# nixie-tube-clock.net
KiCad netlist of a schematic drawn in EAGLE
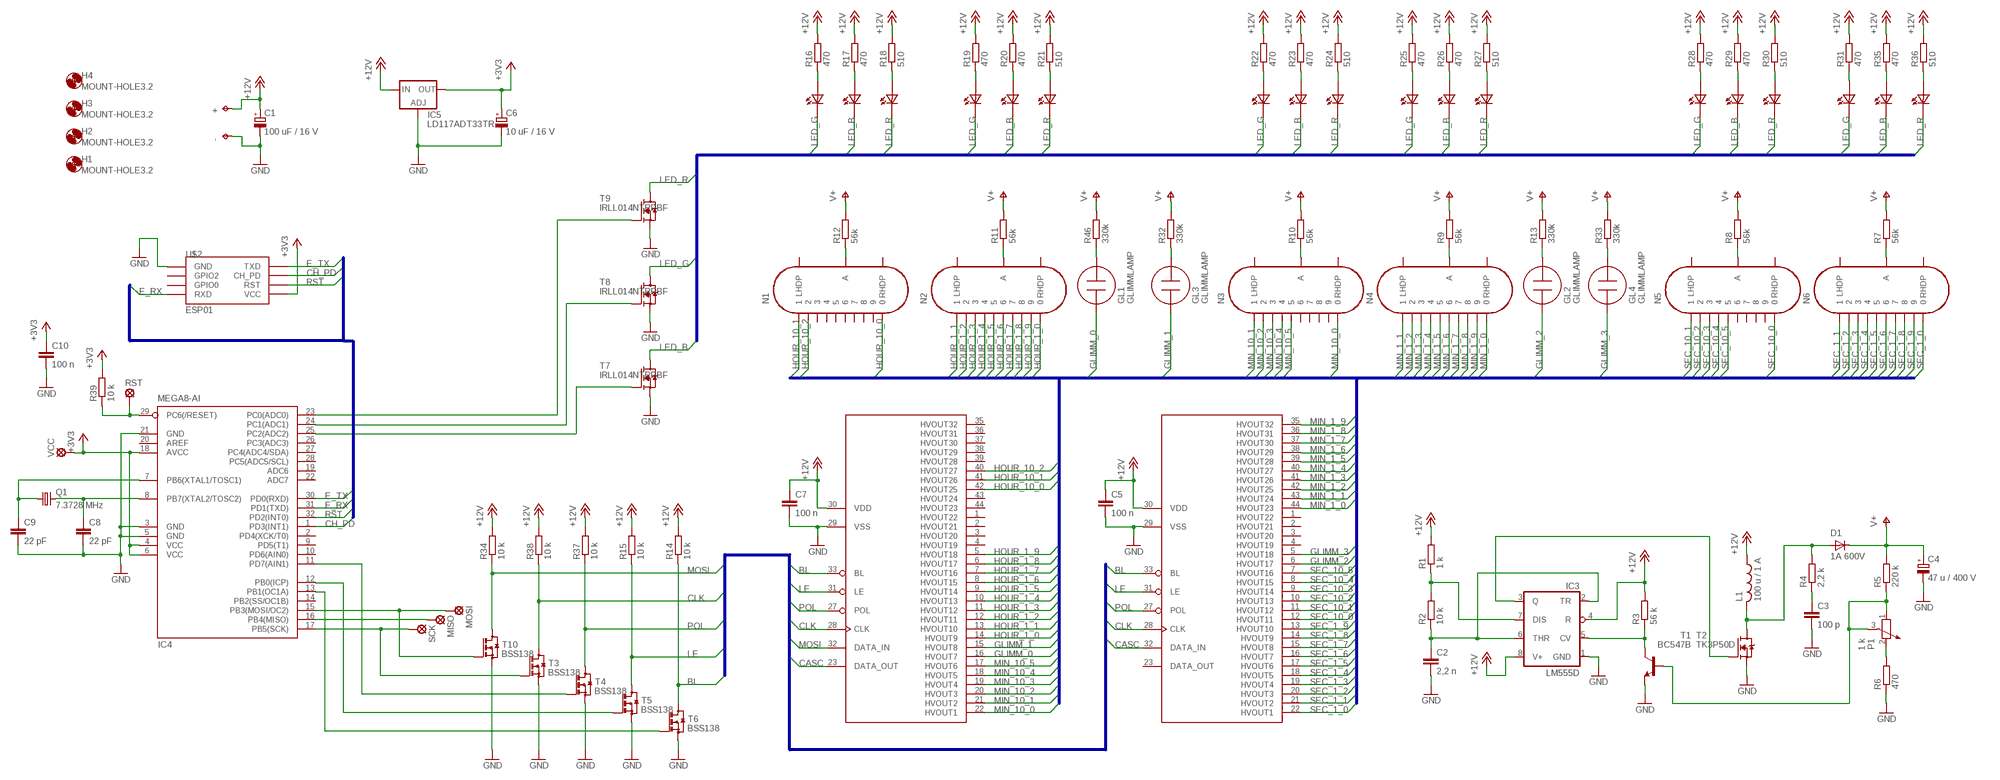
[diagram p0: schematic, sheet 1]

(export (version "E")
  (design (tool "Eeschema 10.0.6"))
  (components
    (comp (ref "+")
      (value "+")
      (footprint "eagle-import:P1-17")
      (libsource (lib "eagle-import") (part "TPPAD1-17"))
    )
    (comp (ref "-")
      (value "-")
      (footprint "eagle-import:P1-17")
      (libsource (lib "eagle-import") (part "TPPAD1-17"))
    )
    (comp (ref "C1")
      (value "100 uF / 16 V")
      (footprint "eagle-import:153CLV-0605")
      (libsource (lib "eagle-import") (part "CPOL-EU153CLV-0605"))
    )
    (comp (ref "C2")
      (value "2,2 n")
      (footprint "eagle-import:C1206")
      (libsource (lib "eagle-import") (part "C-EUC1206"))
    )
    (comp (ref "C3")
      (value "100 p")
      (footprint "eagle-import:C1206")
      (libsource (lib "eagle-import") (part "resistor_C-EUC1206"))
    )
    (comp (ref "C4")
      (value "47 u / 400 V")
      (footprint "eagle-import:E7,5-16")
      (libsource (lib "eagle-import") (part "CPOL-EUE7.5-16"))
    )
    (comp (ref "C5")
      (value "100 n")
      (footprint "eagle-import:C1206")
      (libsource (lib "eagle-import") (part "resistor_C-EUC1206"))
    )
    (comp (ref "C6")
      (value "10 uF / 16 V")
      (footprint "eagle-import:153CLV-0405")
      (libsource (lib "eagle-import") (part "CPOL-EU153CLV-0405"))
    )
    (comp (ref "C7")
      (value "100 n")
      (footprint "eagle-import:C1206")
      (libsource (lib "eagle-import") (part "resistor_C-EUC1206"))
    )
    (comp (ref "C8")
      (value "22 pF")
      (footprint "eagle-import:C1206")
      (libsource (lib "eagle-import") (part "resistor_C-EUC1206"))
    )
    (comp (ref "C9")
      (value "22 pF")
      (footprint "eagle-import:C1206")
      (libsource (lib "eagle-import") (part "resistor_C-EUC1206"))
    )
    (comp (ref "C10")
      (value "100 n")
      (footprint "eagle-import:C1206")
      (libsource (lib "eagle-import") (part "resistor_C-EUC1206"))
    )
    (comp (ref "D1")
      (value "1A 600V")
      (footprint "eagle-import:SMA-DO214AC")
      (libsource (lib "eagle-import") (part "GF1"))
    )
    (comp (ref "GL1")
      (value "GLIMMLAMP")
      (footprint "eagle-import:GLIMMLAMP")
      (libsource (lib "eagle-import") (part "GLIMMLAMP"))
    )
    (comp (ref "GL2")
      (value "GLIMMLAMP")
      (footprint "eagle-import:GLIMMLAMP")
      (libsource (lib "eagle-import") (part "GLIMMLAMP"))
    )
    (comp (ref "GL3")
      (value "GLIMMLAMP")
      (footprint "eagle-import:GLIMMLAMP")
      (libsource (lib "eagle-import") (part "GLIMMLAMP"))
    )
    (comp (ref "GL4")
      (value "GLIMMLAMP")
      (footprint "eagle-import:GLIMMLAMP")
      (libsource (lib "eagle-import") (part "GLIMMLAMP"))
    )
    (comp (ref "H1")
      (value "MOUNT-HOLE3.2")
      (footprint "eagle-import:3,2")
      (libsource (lib "eagle-import") (part "MOUNT-HOLE3.2"))
    )
    (comp (ref "H2")
      (value "MOUNT-HOLE3.2")
      (footprint "eagle-import:3,2")
      (libsource (lib "eagle-import") (part "MOUNT-HOLE3.2"))
    )
    (comp (ref "H3")
      (value "MOUNT-HOLE3.2")
      (footprint "eagle-import:3,2")
      (libsource (lib "eagle-import") (part "MOUNT-HOLE3.2"))
    )
    (comp (ref "H4")
      (value "MOUNT-HOLE3.2")
      (footprint "eagle-import:3,2")
      (libsource (lib "eagle-import") (part "MOUNT-HOLE3.2"))
    )
    (comp (ref "IC1")
      (value "HV5622QC")
      (footprint "eagle-import:PQFP44")
      (libsource (lib "eagle-import") (part "HV5622QC"))
    )
    (comp (ref "IC2")
      (value "HV5622QC")
      (footprint "eagle-import:PQFP44")
      (libsource (lib "eagle-import") (part "HV5622QC"))
    )
    (comp (ref "IC3")
      (value "LM555D")
      (footprint "eagle-import:SO08")
      (libsource (lib "eagle-import") (part "555DLM"))
    )
    (comp (ref "IC4")
      (value "MEGA8-AI")
      (footprint "eagle-import:TQFP32-08")
      (fields (field (name "MPN") "ATMEGA8-16AU"))
      (libsource (lib "eagle-import") (part "MEGA8-AI"))
    )
    (comp (ref "IC5")
      (value "LD117ADT33TR")
      (footprint "eagle-import:DPACK")
      (libsource (lib "eagle-import") (part "LD117A?DT33TR"))
    )
    (comp (ref "L1")
      (value "100 u / 1 A")
      (footprint "eagle-import:L_V_8.7X12_RM5.0")
      (libsource (lib "eagle-import") (part "L_V_8.7X12_RM5.0"))
    )
    (comp (ref "MISO")
      (value "MISO")
      (footprint "eagle-import:SE11")
      (libsource (lib "eagle-import") (part "SE11"))
    )
    (comp (ref "MOSI")
      (value "MOSI")
      (footprint "eagle-import:SE11")
      (libsource (lib "eagle-import") (part "SE11"))
    )
    (comp (ref "N1")
      (value "IN-14")
      (footprint "eagle-import:IN-14")
      (libsource (lib "eagle-import") (part "IN-14"))
    )
    (comp (ref "N2")
      (value "IN-14")
      (footprint "eagle-import:IN-14")
      (libsource (lib "eagle-import") (part "IN-14"))
    )
    (comp (ref "N3")
      (value "IN-14")
      (footprint "eagle-import:IN-14")
      (libsource (lib "eagle-import") (part "IN-14"))
    )
    (comp (ref "N4")
      (value "IN-14")
      (footprint "eagle-import:IN-14")
      (libsource (lib "eagle-import") (part "IN-14"))
    )
    (comp (ref "N5")
      (value "IN-14")
      (footprint "eagle-import:IN-14")
      (libsource (lib "eagle-import") (part "IN-14"))
    )
    (comp (ref "N6")
      (value "IN-14")
      (footprint "eagle-import:IN-14")
      (libsource (lib "eagle-import") (part "IN-14"))
    )
    (comp (ref "P1")
      (value "1 k")
      (footprint "eagle-import:PT-10")
      (libsource (lib "eagle-import") (part "POTENTIOMETER_PT-10"))
    )
    (comp (ref "Q1")
      (value "7.3728 MHz")
      (footprint "eagle-import:HC49_S")
      (libsource (lib "eagle-import") (part "CRYSTALHC49S"))
    )
    (comp (ref "R1")
      (value "1 k")
      (footprint "eagle-import:R1206")
      (libsource (lib "eagle-import") (part "R-EU_R1206"))
    )
    (comp (ref "R2")
      (value "10 k")
      (footprint "eagle-import:R1206")
      (libsource (lib "eagle-import") (part "R-EU_R1206"))
    )
    (comp (ref "R3")
      (value "56 k")
      (footprint "eagle-import:R1206")
      (libsource (lib "eagle-import") (part "R-EU_R1206"))
    )
    (comp (ref "R4")
      (value "2,2 k")
      (footprint "eagle-import:R1206")
      (libsource (lib "eagle-import") (part "R-EU_R1206"))
    )
    (comp (ref "R5")
      (value "220 k")
      (footprint "eagle-import:R1206")
      (libsource (lib "eagle-import") (part "R-EU_R1206"))
    )
    (comp (ref "R6")
      (value "470")
      (footprint "eagle-import:R1206")
      (libsource (lib "eagle-import") (part "R-EU_R1206"))
    )
    (comp (ref "R7")
      (value "56k")
      (footprint "eagle-import:R1206")
      (libsource (lib "eagle-import") (part "R-EU_R1206"))
    )
    (comp (ref "R8")
      (value "56k")
      (footprint "eagle-import:R1206")
      (libsource (lib "eagle-import") (part "R-EU_R1206"))
    )
    (comp (ref "R9")
      (value "56k")
      (footprint "eagle-import:R1206")
      (libsource (lib "eagle-import") (part "R-EU_R1206"))
    )
    (comp (ref "R10")
      (value "56k")
      (footprint "eagle-import:R1206")
      (libsource (lib "eagle-import") (part "R-EU_R1206"))
    )
    (comp (ref "R11")
      (value "56k")
      (footprint "eagle-import:R1206")
      (libsource (lib "eagle-import") (part "R-EU_R1206"))
    )
    (comp (ref "R12")
      (value "56k")
      (footprint "eagle-import:R1206")
      (libsource (lib "eagle-import") (part "R-EU_R1206"))
    )
    (comp (ref "R13")
      (value "330k")
      (footprint "eagle-import:R1206")
      (libsource (lib "eagle-import") (part "R-EU_R1206"))
    )
    (comp (ref "R14")
      (value "10 k")
      (footprint "eagle-import:R1206")
      (libsource (lib "eagle-import") (part "R-EU_R1206"))
    )
    (comp (ref "R15")
      (value "10 k")
      (footprint "eagle-import:R1206")
      (libsource (lib "eagle-import") (part "R-EU_R1206"))
    )
    (comp (ref "R16")
      (value "470")
      (footprint "eagle-import:R1206")
      (libsource (lib "eagle-import") (part "R-EU_R1206"))
    )
    (comp (ref "R17")
      (value "470")
      (footprint "eagle-import:R1206")
      (libsource (lib "eagle-import") (part "R-EU_R1206"))
    )
    (comp (ref "R18")
      (value "510")
      (footprint "eagle-import:R1206")
      (libsource (lib "eagle-import") (part "R-EU_R1206"))
    )
    (comp (ref "R19")
      (value "470")
      (footprint "eagle-import:R1206")
      (libsource (lib "eagle-import") (part "R-EU_R1206"))
    )
    (comp (ref "R20")
      (value "470")
      (footprint "eagle-import:R1206")
      (libsource (lib "eagle-import") (part "R-EU_R1206"))
    )
    (comp (ref "R21")
      (value "510")
      (footprint "eagle-import:R1206")
      (libsource (lib "eagle-import") (part "R-EU_R1206"))
    )
    (comp (ref "R22")
      (value "470")
      (footprint "eagle-import:R1206")
      (libsource (lib "eagle-import") (part "R-EU_R1206"))
    )
    (comp (ref "R23")
      (value "470")
      (footprint "eagle-import:R1206")
      (libsource (lib "eagle-import") (part "R-EU_R1206"))
    )
    (comp (ref "R24")
      (value "510")
      (footprint "eagle-import:R1206")
      (libsource (lib "eagle-import") (part "R-EU_R1206"))
    )
    (comp (ref "R25")
      (value "470")
      (footprint "eagle-import:R1206")
      (libsource (lib "eagle-import") (part "R-EU_R1206"))
    )
    (comp (ref "R26")
      (value "470")
      (footprint "eagle-import:R1206")
      (libsource (lib "eagle-import") (part "R-EU_R1206"))
    )
    (comp (ref "R27")
      (value "510")
      (footprint "eagle-import:R1206")
      (libsource (lib "eagle-import") (part "R-EU_R1206"))
    )
    (comp (ref "R28")
      (value "470")
      (footprint "eagle-import:R1206")
      (libsource (lib "eagle-import") (part "R-EU_R1206"))
    )
    (comp (ref "R29")
      (value "470")
      (footprint "eagle-import:R1206")
      (libsource (lib "eagle-import") (part "R-EU_R1206"))
    )
    (comp (ref "R30")
      (value "510")
      (footprint "eagle-import:R1206")
      (libsource (lib "eagle-import") (part "R-EU_R1206"))
    )
    (comp (ref "R31")
      (value "470")
      (footprint "eagle-import:R1206")
      (libsource (lib "eagle-import") (part "R-EU_R1206"))
    )
    (comp (ref "R32")
      (value "330k")
      (footprint "eagle-import:R1206")
      (libsource (lib "eagle-import") (part "R-EU_R1206"))
    )
    (comp (ref "R33")
      (value "330k")
      (footprint "eagle-import:R1206")
      (libsource (lib "eagle-import") (part "R-EU_R1206"))
    )
    (comp (ref "R34")
      (value "10 k")
      (footprint "eagle-import:R1206")
      (libsource (lib "eagle-import") (part "R-EU_R1206"))
    )
    (comp (ref "R35")
      (value "470")
      (footprint "eagle-import:R1206")
      (libsource (lib "eagle-import") (part "R-EU_R1206"))
    )
    (comp (ref "R36")
      (value "510")
      (footprint "eagle-import:R1206")
      (libsource (lib "eagle-import") (part "R-EU_R1206"))
    )
    (comp (ref "R37")
      (value "10 k")
      (footprint "eagle-import:R1206")
      (libsource (lib "eagle-import") (part "R-EU_R1206"))
    )
    (comp (ref "R38")
      (value "10 k")
      (footprint "eagle-import:R1206")
      (libsource (lib "eagle-import") (part "R-EU_R1206"))
    )
    (comp (ref "R39")
      (value "10 k")
      (footprint "eagle-import:R1206")
      (libsource (lib "eagle-import") (part "R-EU_R1206"))
    )
    (comp (ref "R46")
      (value "330k")
      (footprint "eagle-import:R1206")
      (libsource (lib "eagle-import") (part "R-EU_R1206"))
    )
    (comp (ref "RST")
      (value "RST")
      (footprint "eagle-import:SE11")
      (libsource (lib "eagle-import") (part "SE11"))
    )
    (comp (ref "SCK")
      (value "SCK")
      (footprint "eagle-import:SE11")
      (libsource (lib "eagle-import") (part "SE11"))
    )
    (comp (ref "T1")
      (value "BC547B")
      (footprint "eagle-import:SOT23-BEC")
      (libsource (lib "eagle-import") (part "-NPN-SOT23-BECBC817"))
    )
    (comp (ref "T2")
      (value "TK3P50D")
      (footprint "eagle-import:TO252")
      (libsource (lib "eagle-import") (part "IRFR320PBF"))
    )
    (comp (ref "T3")
      (value "BSS138")
      (footprint "eagle-import:SOT23")
      (libsource (lib "eagle-import") (part "BSS123"))
    )
    (comp (ref "T4")
      (value "BSS138")
      (footprint "eagle-import:SOT23")
      (libsource (lib "eagle-import") (part "BSS123"))
    )
    (comp (ref "T5")
      (value "BSS138")
      (footprint "eagle-import:SOT23")
      (libsource (lib "eagle-import") (part "BSS123"))
    )
    (comp (ref "T6")
      (value "BSS138")
      (footprint "eagle-import:SOT23")
      (libsource (lib "eagle-import") (part "BSS123"))
    )
    (comp (ref "T7")
      (value "IRLL014NTRPBF")
      (footprint "eagle-import:SOT223")
      (libsource (lib "eagle-import") (part "IRLL014NTRPBF"))
    )
    (comp (ref "T8")
      (value "IRLL014NTRPBF")
      (footprint "eagle-import:SOT223")
      (libsource (lib "eagle-import") (part "IRLL014NTRPBF"))
    )
    (comp (ref "T9")
      (value "IRLL014NTRPBF")
      (footprint "eagle-import:SOT223")
      (libsource (lib "eagle-import") (part "IRLL014NTRPBF"))
    )
    (comp (ref "T10")
      (value "BSS138")
      (footprint "eagle-import:SOT23")
      (libsource (lib "eagle-import") (part "BSS123"))
    )
    (comp (ref "U$1")
      (value "OF-SMD5060RGB")
      (footprint "eagle-import:OF-SMD5060RGB")
      (libsource (lib "eagle-import") (part "OF-SMD5060RGB"))
    )
    (comp (ref "U$2")
      (value "ESP01")
      (footprint "eagle-import:ESP01")
      (libsource (lib "eagle-import") (part "ESP01"))
    )
    (comp (ref "U$3")
      (value "OF-SMD5060RGB")
      (footprint "eagle-import:OF-SMD5060RGB")
      (libsource (lib "eagle-import") (part "OF-SMD5060RGB"))
    )
    (comp (ref "U$4")
      (value "OF-SMD5060RGB")
      (footprint "eagle-import:OF-SMD5060RGB")
      (libsource (lib "eagle-import") (part "OF-SMD5060RGB"))
    )
    (comp (ref "U$5")
      (value "OF-SMD5060RGB")
      (footprint "eagle-import:OF-SMD5060RGB")
      (libsource (lib "eagle-import") (part "OF-SMD5060RGB"))
    )
    (comp (ref "U$6")
      (value "OF-SMD5060RGB")
      (footprint "eagle-import:OF-SMD5060RGB")
      (libsource (lib "eagle-import") (part "OF-SMD5060RGB"))
    )
    (comp (ref "U$7")
      (value "OF-SMD5060RGB")
      (footprint "eagle-import:OF-SMD5060RGB")
      (libsource (lib "eagle-import") (part "OF-SMD5060RGB"))
    )
    (comp (ref "VCC")
      (value "VCC")
      (footprint "eagle-import:SE11")
      (libsource (lib "eagle-import") (part "SE11"))
    )
  )
  (nets
    (net (code "1") (name "+3V3") (class "Default")
      (node (ref "C10") (pin "1") (pinfunction "1_1") (pintype "passive"))
      (node (ref "C6") (pin "+") (pinfunction "+_+") (pintype "passive"))
      (node (ref "IC4") (pin "18") (pinfunction "AVCC_18") (pintype "power_in"))
      (node (ref "IC4") (pin "4") (pinfunction "VCC_4") (pintype "power_in"))
      (node (ref "IC4") (pin "6") (pinfunction "VCC_6") (pintype "power_in"))
      (node (ref "IC5") (pin "4") (pinfunction "OUT_4") (pintype "passive"))
      (node (ref "R39") (pin "2") (pinfunction "2_2") (pintype "passive"))
      (node (ref "U$2") (pin "VCC") (pinfunction "VCC_VCC") (pintype "bidirectional"))
      (node (ref "VCC") (pin "MP") (pinfunction "MP_MP") (pintype "passive"))
    )
    (net (code "2") (name "+12V") (class "Default")
      (node (ref "+") (pin "TP") (pinfunction "TP_TP") (pintype "input"))
      (node (ref "C1") (pin "+") (pinfunction "+_+") (pintype "passive"))
      (node (ref "C5") (pin "1") (pinfunction "1_1") (pintype "passive"))
      (node (ref "C7") (pin "1") (pinfunction "1_1") (pintype "passive"))
      (node (ref "IC1") (pin "30") (pinfunction "VDD_30") (pintype "power_in"))
      (node (ref "IC2") (pin "30") (pinfunction "VDD_30") (pintype "power_in"))
      (node (ref "IC3") (pin "4") (pinfunction "R_4") (pintype "input"))
      (node (ref "IC3") (pin "8") (pinfunction "V+_8") (pintype "power_in"))
      (node (ref "IC5") (pin "3") (pinfunction "IN_3") (pintype "input"))
      (node (ref "L1") (pin "P$1") (pinfunction "1_P$1") (pintype "passive"))
      (node (ref "R1") (pin "2") (pinfunction "2_2") (pintype "passive"))
      (node (ref "R14") (pin "2") (pinfunction "2_2") (pintype "passive"))
      (node (ref "R15") (pin "2") (pinfunction "2_2") (pintype "passive"))
      (node (ref "R16") (pin "2") (pinfunction "2_2") (pintype "passive"))
      (node (ref "R17") (pin "2") (pinfunction "2_2") (pintype "passive"))
      (node (ref "R18") (pin "2") (pinfunction "2_2") (pintype "passive"))
      (node (ref "R19") (pin "2") (pinfunction "2_2") (pintype "passive"))
      (node (ref "R20") (pin "2") (pinfunction "2_2") (pintype "passive"))
      (node (ref "R21") (pin "2") (pinfunction "2_2") (pintype "passive"))
      (node (ref "R22") (pin "2") (pinfunction "2_2") (pintype "passive"))
      (node (ref "R23") (pin "2") (pinfunction "2_2") (pintype "passive"))
      (node (ref "R24") (pin "2") (pinfunction "2_2") (pintype "passive"))
      (node (ref "R25") (pin "2") (pinfunction "2_2") (pintype "passive"))
      (node (ref "R26") (pin "2") (pinfunction "2_2") (pintype "passive"))
      (node (ref "R27") (pin "2") (pinfunction "2_2") (pintype "passive"))
      (node (ref "R28") (pin "2") (pinfunction "2_2") (pintype "passive"))
      (node (ref "R29") (pin "2") (pinfunction "2_2") (pintype "passive"))
      (node (ref "R3") (pin "2") (pinfunction "2_2") (pintype "passive"))
      (node (ref "R30") (pin "2") (pinfunction "2_2") (pintype "passive"))
      (node (ref "R31") (pin "2") (pinfunction "2_2") (pintype "passive"))
      (node (ref "R34") (pin "2") (pinfunction "2_2") (pintype "passive"))
      (node (ref "R35") (pin "2") (pinfunction "2_2") (pintype "passive"))
      (node (ref "R36") (pin "2") (pinfunction "2_2") (pintype "passive"))
      (node (ref "R37") (pin "2") (pinfunction "2_2") (pintype "passive"))
      (node (ref "R38") (pin "2") (pinfunction "2_2") (pintype "passive"))
    )
    (net (code "3") (name "/BL") (class "Default")
      (node (ref "IC1") (pin "33") (pinfunction "BL_33") (pintype "input"))
      (node (ref "IC2") (pin "33") (pinfunction "BL_33") (pintype "input"))
      (node (ref "R14") (pin "1") (pinfunction "1_1") (pintype "passive"))
      (node (ref "T6") (pin "3") (pinfunction "D_3") (pintype "passive"))
    )
    (net (code "4") (name "/CASC") (class "Default")
      (node (ref "IC1") (pin "23") (pinfunction "DATA_OUT_23") (pintype "output"))
      (node (ref "IC2") (pin "32") (pinfunction "DATA_IN_32") (pintype "input"))
    )
    (net (code "5") (name "/CH_PD") (class "Default")
      (node (ref "IC4") (pin "1") (pinfunction "PD3(INT1)_1") (pintype "bidirectional"))
      (node (ref "U$2") (pin "CH_PD") (pinfunction "CH_PD_CH_PD") (pintype "bidirectional"))
    )
    (net (code "6") (name "/CLK") (class "Default")
      (node (ref "IC1") (pin "28") (pinfunction "CLK_28") (pintype "input"))
      (node (ref "IC2") (pin "28") (pinfunction "CLK_28") (pintype "input"))
      (node (ref "R38") (pin "1") (pinfunction "1_1") (pintype "passive"))
      (node (ref "T3") (pin "3") (pinfunction "D_3") (pintype "passive"))
    )
    (net (code "7") (name "/E_RX") (class "Default")
      (node (ref "IC4") (pin "31") (pinfunction "PD1(TXD)_31") (pintype "bidirectional"))
      (node (ref "U$2") (pin "RX") (pinfunction "RXD_RX") (pintype "bidirectional"))
    )
    (net (code "8") (name "/E_TX") (class "Default")
      (node (ref "IC4") (pin "30") (pinfunction "PD0(RXD)_30") (pintype "bidirectional"))
      (node (ref "U$2") (pin "TX") (pinfunction "TXD_TX") (pintype "bidirectional"))
    )
    (net (code "9") (name "/GLIMM_0") (class "Default")
      (node (ref "GL1") (pin "C") (pinfunction "P$2_C") (pintype "passive"))
      (node (ref "IC1") (pin "16") (pinfunction "HVOUT7_16") (pintype "bidirectional"))
    )
    (net (code "10") (name "/GLIMM_1") (class "Default")
      (node (ref "GL3") (pin "C") (pinfunction "P$2_C") (pintype "passive"))
      (node (ref "IC1") (pin "15") (pinfunction "HVOUT8_15") (pintype "bidirectional"))
    )
    (net (code "11") (name "/GLIMM_2") (class "Default")
      (node (ref "GL2") (pin "C") (pinfunction "P$2_C") (pintype "passive"))
      (node (ref "IC2") (pin "6") (pinfunction "HVOUT17_6") (pintype "bidirectional"))
    )
    (net (code "12") (name "/GLIMM_3") (class "Default")
      (node (ref "GL4") (pin "C") (pinfunction "P$2_C") (pintype "passive"))
      (node (ref "IC2") (pin "5") (pinfunction "HVOUT18_5") (pintype "bidirectional"))
    )
    (net (code "13") (name "/HOUR_1_0") (class "Default")
      (node (ref "IC1") (pin "14") (pinfunction "HVOUT9_14") (pintype "bidirectional"))
      (node (ref "N2") (pin "0") (pinfunction "0_0") (pintype "bidirectional"))
    )
    (net (code "14") (name "/HOUR_1_1") (class "Default")
      (node (ref "IC1") (pin "13") (pinfunction "HVOUT10_13") (pintype "bidirectional"))
      (node (ref "N2") (pin "1") (pinfunction "1_1") (pintype "bidirectional"))
    )
    (net (code "15") (name "/HOUR_1_2") (class "Default")
      (node (ref "IC1") (pin "12") (pinfunction "HVOUT11_12") (pintype "bidirectional"))
      (node (ref "N2") (pin "2") (pinfunction "2_2") (pintype "bidirectional"))
    )
    (net (code "16") (name "/HOUR_1_3") (class "Default")
      (node (ref "IC1") (pin "11") (pinfunction "HVOUT12_11") (pintype "bidirectional"))
      (node (ref "N2") (pin "3") (pinfunction "3_3") (pintype "bidirectional"))
    )
    (net (code "17") (name "/HOUR_1_4") (class "Default")
      (node (ref "IC1") (pin "10") (pinfunction "HVOUT13_10") (pintype "bidirectional"))
      (node (ref "N2") (pin "4") (pinfunction "4_4") (pintype "bidirectional"))
    )
    (net (code "18") (name "/HOUR_1_5") (class "Default")
      (node (ref "IC1") (pin "9") (pinfunction "HVOUT14_9") (pintype "bidirectional"))
      (node (ref "N2") (pin "5") (pinfunction "5_5") (pintype "bidirectional"))
    )
    (net (code "19") (name "/HOUR_1_6") (class "Default")
      (node (ref "IC1") (pin "8") (pinfunction "HVOUT15_8") (pintype "bidirectional"))
      (node (ref "N2") (pin "6") (pinfunction "6_6") (pintype "bidirectional"))
    )
    (net (code "20") (name "/HOUR_1_7") (class "Default")
      (node (ref "IC1") (pin "7") (pinfunction "HVOUT16_7") (pintype "bidirectional"))
      (node (ref "N2") (pin "7") (pinfunction "7_7") (pintype "bidirectional"))
    )
    (net (code "21") (name "/HOUR_1_8") (class "Default")
      (node (ref "IC1") (pin "6") (pinfunction "HVOUT17_6") (pintype "bidirectional"))
      (node (ref "N2") (pin "8") (pinfunction "8_8") (pintype "bidirectional"))
    )
    (net (code "22") (name "/HOUR_1_9") (class "Default")
      (node (ref "IC1") (pin "5") (pinfunction "HVOUT18_5") (pintype "bidirectional"))
      (node (ref "N2") (pin "9") (pinfunction "9_9") (pintype "bidirectional"))
    )
    (net (code "23") (name "/HOUR_10_0") (class "Default")
      (node (ref "IC1") (pin "42") (pinfunction "HVOUT25_42") (pintype "bidirectional"))
      (node (ref "N1") (pin "0") (pinfunction "0_0") (pintype "bidirectional"))
    )
    (net (code "24") (name "/HOUR_10_1") (class "Default")
      (node (ref "IC1") (pin "41") (pinfunction "HVOUT26_41") (pintype "bidirectional"))
      (node (ref "N1") (pin "1") (pinfunction "1_1") (pintype "bidirectional"))
    )
    (net (code "25") (name "/HOUR_10_2") (class "Default")
      (node (ref "IC1") (pin "40") (pinfunction "HVOUT27_40") (pintype "bidirectional"))
      (node (ref "N1") (pin "2") (pinfunction "2_2") (pintype "bidirectional"))
    )
    (net (code "26") (name "/LE") (class "Default")
      (node (ref "IC1") (pin "31") (pinfunction "LE_31") (pintype "input"))
      (node (ref "IC2") (pin "31") (pinfunction "LE_31") (pintype "input"))
      (node (ref "R15") (pin "1") (pinfunction "1_1") (pintype "passive"))
      (node (ref "T5") (pin "3") (pinfunction "D_3") (pintype "passive"))
    )
    (net (code "27") (name "/LED_B") (class "Default")
      (node (ref "T7") (pin "2") (pinfunction "D_2") (pintype "passive"))
      (node (ref "T7") (pin "4") (pinfunction "D_4") (pintype "passive"))
      (node (ref "U$1") (pin "B_CATH") (pinfunction "CATH_B_CATH") (pintype "bidirectional"))
      (node (ref "U$3") (pin "B_CATH") (pinfunction "CATH_B_CATH") (pintype "bidirectional"))
      (node (ref "U$4") (pin "B_CATH") (pinfunction "CATH_B_CATH") (pintype "bidirectional"))
      (node (ref "U$5") (pin "B_CATH") (pinfunction "CATH_B_CATH") (pintype "bidirectional"))
      (node (ref "U$6") (pin "B_CATH") (pinfunction "CATH_B_CATH") (pintype "bidirectional"))
      (node (ref "U$7") (pin "B_CATH") (pinfunction "CATH_B_CATH") (pintype "bidirectional"))
    )
    (net (code "28") (name "/LED_G") (class "Default")
      (node (ref "T8") (pin "2") (pinfunction "D_2") (pintype "passive"))
      (node (ref "T8") (pin "4") (pinfunction "D_4") (pintype "passive"))
      (node (ref "U$1") (pin "G_CATH") (pinfunction "CATH_G_CATH") (pintype "bidirectional"))
      (node (ref "U$3") (pin "G_CATH") (pinfunction "CATH_G_CATH") (pintype "bidirectional"))
      (node (ref "U$4") (pin "G_CATH") (pinfunction "CATH_G_CATH") (pintype "bidirectional"))
      (node (ref "U$5") (pin "G_CATH") (pinfunction "CATH_G_CATH") (pintype "bidirectional"))
      (node (ref "U$6") (pin "G_CATH") (pinfunction "CATH_G_CATH") (pintype "bidirectional"))
      (node (ref "U$7") (pin "G_CATH") (pinfunction "CATH_G_CATH") (pintype "bidirectional"))
    )
    (net (code "29") (name "/LED_R") (class "Default")
      (node (ref "T9") (pin "2") (pinfunction "D_2") (pintype "passive"))
      (node (ref "T9") (pin "4") (pinfunction "D_4") (pintype "passive"))
      (node (ref "U$1") (pin "R_CATH") (pinfunction "CATH_R_CATH") (pintype "bidirectional"))
      (node (ref "U$3") (pin "R_CATH") (pinfunction "CATH_R_CATH") (pintype "bidirectional"))
      (node (ref "U$4") (pin "R_CATH") (pinfunction "CATH_R_CATH") (pintype "bidirectional"))
      (node (ref "U$5") (pin "R_CATH") (pinfunction "CATH_R_CATH") (pintype "bidirectional"))
      (node (ref "U$6") (pin "R_CATH") (pinfunction "CATH_R_CATH") (pintype "bidirectional"))
      (node (ref "U$7") (pin "R_CATH") (pinfunction "CATH_R_CATH") (pintype "bidirectional"))
    )
    (net (code "30") (name "/MIN_1_0") (class "Default")
      (node (ref "IC2") (pin "44") (pinfunction "HVOUT23_44") (pintype "bidirectional"))
      (node (ref "N4") (pin "0") (pinfunction "0_0") (pintype "bidirectional"))
    )
    (net (code "31") (name "/MIN_1_1") (class "Default")
      (node (ref "IC2") (pin "43") (pinfunction "HVOUT24_43") (pintype "bidirectional"))
      (node (ref "N4") (pin "1") (pinfunction "1_1") (pintype "bidirectional"))
    )
    (net (code "32") (name "/MIN_1_2") (class "Default")
      (node (ref "IC2") (pin "42") (pinfunction "HVOUT25_42") (pintype "bidirectional"))
      (node (ref "N4") (pin "2") (pinfunction "2_2") (pintype "bidirectional"))
    )
    (net (code "33") (name "/MIN_1_3") (class "Default")
      (node (ref "IC2") (pin "41") (pinfunction "HVOUT26_41") (pintype "bidirectional"))
      (node (ref "N4") (pin "3") (pinfunction "3_3") (pintype "bidirectional"))
    )
    (net (code "34") (name "/MIN_1_4") (class "Default")
      (node (ref "IC2") (pin "40") (pinfunction "HVOUT27_40") (pintype "bidirectional"))
      (node (ref "N4") (pin "4") (pinfunction "4_4") (pintype "bidirectional"))
    )
    (net (code "35") (name "/MIN_1_5") (class "Default")
      (node (ref "IC2") (pin "39") (pinfunction "HVOUT28_39") (pintype "bidirectional"))
      (node (ref "N4") (pin "5") (pinfunction "5_5") (pintype "bidirectional"))
    )
    (net (code "36") (name "/MIN_1_6") (class "Default")
      (node (ref "IC2") (pin "38") (pinfunction "HVOUT29_38") (pintype "bidirectional"))
      (node (ref "N4") (pin "6") (pinfunction "6_6") (pintype "bidirectional"))
    )
    (net (code "37") (name "/MIN_1_7") (class "Default")
      (node (ref "IC2") (pin "37") (pinfunction "HVOUT30_37") (pintype "bidirectional"))
      (node (ref "N4") (pin "7") (pinfunction "7_7") (pintype "bidirectional"))
    )
    (net (code "38") (name "/MIN_1_8") (class "Default")
      (node (ref "IC2") (pin "36") (pinfunction "HVOUT31_36") (pintype "bidirectional"))
      (node (ref "N4") (pin "8") (pinfunction "8_8") (pintype "bidirectional"))
    )
    (net (code "39") (name "/MIN_1_9") (class "Default")
      (node (ref "IC2") (pin "35") (pinfunction "HVOUT32_35") (pintype "bidirectional"))
      (node (ref "N4") (pin "9") (pinfunction "9_9") (pintype "bidirectional"))
    )
    (net (code "40") (name "/MIN_10_0") (class "Default")
      (node (ref "IC1") (pin "22") (pinfunction "HVOUT1_22") (pintype "bidirectional"))
      (node (ref "N3") (pin "0") (pinfunction "0_0") (pintype "bidirectional"))
    )
    (net (code "41") (name "/MIN_10_1") (class "Default")
      (node (ref "IC1") (pin "21") (pinfunction "HVOUT2_21") (pintype "bidirectional"))
      (node (ref "N3") (pin "1") (pinfunction "1_1") (pintype "bidirectional"))
    )
    (net (code "42") (name "/MIN_10_2") (class "Default")
      (node (ref "IC1") (pin "20") (pinfunction "HVOUT3_20") (pintype "bidirectional"))
      (node (ref "N3") (pin "2") (pinfunction "2_2") (pintype "bidirectional"))
    )
    (net (code "43") (name "/MIN_10_3") (class "Default")
      (node (ref "IC1") (pin "19") (pinfunction "HVOUT4_19") (pintype "bidirectional"))
      (node (ref "N3") (pin "3") (pinfunction "3_3") (pintype "bidirectional"))
    )
    (net (code "44") (name "/MIN_10_4") (class "Default")
      (node (ref "IC1") (pin "18") (pinfunction "HVOUT5_18") (pintype "bidirectional"))
      (node (ref "N3") (pin "4") (pinfunction "4_4") (pintype "bidirectional"))
    )
    (net (code "45") (name "/MIN_10_5") (class "Default")
      (node (ref "IC1") (pin "17") (pinfunction "HVOUT6_17") (pintype "bidirectional"))
      (node (ref "N3") (pin "5") (pinfunction "5_5") (pintype "bidirectional"))
    )
    (net (code "46") (name "/MOSI") (class "Default")
      (node (ref "IC1") (pin "32") (pinfunction "DATA_IN_32") (pintype "input"))
      (node (ref "R34") (pin "1") (pinfunction "1_1") (pintype "passive"))
      (node (ref "T10") (pin "3") (pinfunction "D_3") (pintype "passive"))
    )
    (net (code "47") (name "/POL") (class "Default")
      (node (ref "IC1") (pin "27") (pinfunction "POL_27") (pintype "input"))
      (node (ref "IC2") (pin "27") (pinfunction "POL_27") (pintype "input"))
      (node (ref "R37") (pin "1") (pinfunction "1_1") (pintype "passive"))
      (node (ref "T4") (pin "3") (pinfunction "D_3") (pintype "passive"))
    )
    (net (code "48") (name "/RST") (class "Default")
      (node (ref "IC4") (pin "32") (pinfunction "PD2(INT0)_32") (pintype "bidirectional"))
      (node (ref "U$2") (pin "RST") (pinfunction "RST_RST") (pintype "bidirectional"))
    )
    (net (code "49") (name "/SEC_1_0") (class "Default")
      (node (ref "IC2") (pin "22") (pinfunction "HVOUT1_22") (pintype "bidirectional"))
      (node (ref "N6") (pin "0") (pinfunction "0_0") (pintype "bidirectional"))
    )
    (net (code "50") (name "/SEC_1_1") (class "Default")
      (node (ref "IC2") (pin "21") (pinfunction "HVOUT2_21") (pintype "bidirectional"))
      (node (ref "N6") (pin "1") (pinfunction "1_1") (pintype "bidirectional"))
    )
    (net (code "51") (name "/SEC_1_2") (class "Default")
      (node (ref "IC2") (pin "20") (pinfunction "HVOUT3_20") (pintype "bidirectional"))
      (node (ref "N6") (pin "2") (pinfunction "2_2") (pintype "bidirectional"))
    )
    (net (code "52") (name "/SEC_1_3") (class "Default")
      (node (ref "IC2") (pin "19") (pinfunction "HVOUT4_19") (pintype "bidirectional"))
      (node (ref "N6") (pin "3") (pinfunction "3_3") (pintype "bidirectional"))
    )
    (net (code "53") (name "/SEC_1_4") (class "Default")
      (node (ref "IC2") (pin "18") (pinfunction "HVOUT5_18") (pintype "bidirectional"))
      (node (ref "N6") (pin "4") (pinfunction "4_4") (pintype "bidirectional"))
    )
    (net (code "54") (name "/SEC_1_5") (class "Default")
      (node (ref "IC2") (pin "17") (pinfunction "HVOUT6_17") (pintype "bidirectional"))
      (node (ref "N6") (pin "5") (pinfunction "5_5") (pintype "bidirectional"))
    )
    (net (code "55") (name "/SEC_1_6") (class "Default")
      (node (ref "IC2") (pin "16") (pinfunction "HVOUT7_16") (pintype "bidirectional"))
      (node (ref "N6") (pin "6") (pinfunction "6_6") (pintype "bidirectional"))
    )
    (net (code "56") (name "/SEC_1_7") (class "Default")
      (node (ref "IC2") (pin "15") (pinfunction "HVOUT8_15") (pintype "bidirectional"))
      (node (ref "N6") (pin "7") (pinfunction "7_7") (pintype "bidirectional"))
    )
    (net (code "57") (name "/SEC_1_8") (class "Default")
      (node (ref "IC2") (pin "14") (pinfunction "HVOUT9_14") (pintype "bidirectional"))
      (node (ref "N6") (pin "8") (pinfunction "8_8") (pintype "bidirectional"))
    )
    (net (code "58") (name "/SEC_1_9") (class "Default")
      (node (ref "IC2") (pin "13") (pinfunction "HVOUT10_13") (pintype "bidirectional"))
      (node (ref "N6") (pin "9") (pinfunction "9_9") (pintype "bidirectional"))
    )
    (net (code "59") (name "/SEC_10_0") (class "Default")
      (node (ref "IC2") (pin "12") (pinfunction "HVOUT11_12") (pintype "bidirectional"))
      (node (ref "N5") (pin "0") (pinfunction "0_0") (pintype "bidirectional"))
    )
    (net (code "60") (name "/SEC_10_1") (class "Default")
      (node (ref "IC2") (pin "11") (pinfunction "HVOUT12_11") (pintype "bidirectional"))
      (node (ref "N5") (pin "1") (pinfunction "1_1") (pintype "bidirectional"))
    )
    (net (code "61") (name "/SEC_10_2") (class "Default")
      (node (ref "IC2") (pin "10") (pinfunction "HVOUT13_10") (pintype "bidirectional"))
      (node (ref "N5") (pin "2") (pinfunction "2_2") (pintype "bidirectional"))
    )
    (net (code "62") (name "/SEC_10_3") (class "Default")
      (node (ref "IC2") (pin "9") (pinfunction "HVOUT14_9") (pintype "bidirectional"))
      (node (ref "N5") (pin "3") (pinfunction "3_3") (pintype "bidirectional"))
    )
    (net (code "63") (name "/SEC_10_4") (class "Default")
      (node (ref "IC2") (pin "8") (pinfunction "HVOUT15_8") (pintype "bidirectional"))
      (node (ref "N5") (pin "4") (pinfunction "4_4") (pintype "bidirectional"))
    )
    (net (code "64") (name "/SEC_10_5") (class "Default")
      (node (ref "IC2") (pin "7") (pinfunction "HVOUT16_7") (pintype "bidirectional"))
      (node (ref "N5") (pin "5") (pinfunction "5_5") (pintype "bidirectional"))
    )
    (net (code "65") (name "GND") (class "Default")
      (node (ref "-") (pin "TP") (pinfunction "TP_TP") (pintype "input"))
      (node (ref "C1") (pin "-") (pinfunction "-_-") (pintype "passive"))
      (node (ref "C10") (pin "2") (pinfunction "2_2") (pintype "passive"))
      (node (ref "C2") (pin "2") (pinfunction "2_2") (pintype "passive"))
      (node (ref "C3") (pin "2") (pinfunction "2_2") (pintype "passive"))
      (node (ref "C4") (pin "-") (pinfunction "-_-") (pintype "passive"))
      (node (ref "C5") (pin "2") (pinfunction "2_2") (pintype "passive"))
      (node (ref "C6") (pin "-") (pinfunction "-_-") (pintype "passive"))
      (node (ref "C7") (pin "2") (pinfunction "2_2") (pintype "passive"))
      (node (ref "C8") (pin "2") (pinfunction "2_2") (pintype "passive"))
      (node (ref "C9") (pin "2") (pinfunction "2_2") (pintype "passive"))
      (node (ref "IC1") (pin "29") (pinfunction "VSS_29") (pintype "power_in"))
      (node (ref "IC2") (pin "29") (pinfunction "VSS_29") (pintype "power_in"))
      (node (ref "IC3") (pin "1") (pinfunction "GND_1") (pintype "power_in"))
      (node (ref "IC4") (pin "21") (pinfunction "GND_21") (pintype "power_in"))
      (node (ref "IC4") (pin "3") (pinfunction "GND_3") (pintype "power_in"))
      (node (ref "IC4") (pin "5") (pinfunction "GND_5") (pintype "power_in"))
      (node (ref "IC5") (pin "1") (pinfunction "ADJ_1") (pintype "input"))
      (node (ref "R6") (pin "1") (pinfunction "1_1") (pintype "passive"))
      (node (ref "T1") (pin "E") (pinfunction "E_E") (pintype "passive"))
      (node (ref "T10") (pin "2") (pinfunction "S_2") (pintype "passive"))
      (node (ref "T2") (pin "2") (pinfunction "S_2") (pintype "passive"))
      (node (ref "T3") (pin "2") (pinfunction "S_2") (pintype "passive"))
      (node (ref "T4") (pin "2") (pinfunction "S_2") (pintype "passive"))
      (node (ref "T5") (pin "2") (pinfunction "S_2") (pintype "passive"))
      (node (ref "T6") (pin "2") (pinfunction "S_2") (pintype "passive"))
      (node (ref "T7") (pin "3") (pinfunction "S_3") (pintype "passive"))
      (node (ref "T8") (pin "3") (pinfunction "S_3") (pintype "passive"))
      (node (ref "T9") (pin "3") (pinfunction "S_3") (pintype "passive"))
      (node (ref "U$2") (pin "GND") (pinfunction "GND_GND") (pintype "bidirectional"))
    )
    (net (code "66") (name "Net-(C3-Pad1)") (class "Default")
      (node (ref "C3") (pin "1") (pinfunction "1_1") (pintype "passive"))
      (node (ref "R4") (pin "1") (pinfunction "1_1") (pintype "passive"))
    )
    (net (code "67") (name "Net-(GL1-P$1)") (class "Default")
      (node (ref "GL1") (pin "A") (pinfunction "P$1_A") (pintype "passive"))
      (node (ref "R46") (pin "1") (pinfunction "1_1") (pintype "passive"))
    )
    (net (code "68") (name "Net-(GL2-P$1)") (class "Default")
      (node (ref "GL2") (pin "A") (pinfunction "P$1_A") (pintype "passive"))
      (node (ref "R13") (pin "1") (pinfunction "1_1") (pintype "passive"))
    )
    (net (code "69") (name "Net-(GL3-P$1)") (class "Default")
      (node (ref "GL3") (pin "A") (pinfunction "P$1_A") (pintype "passive"))
      (node (ref "R32") (pin "1") (pinfunction "1_1") (pintype "passive"))
    )
    (net (code "70") (name "Net-(GL4-P$1)") (class "Default")
      (node (ref "GL4") (pin "A") (pinfunction "P$1_A") (pintype "passive"))
      (node (ref "R33") (pin "1") (pinfunction "1_1") (pintype "passive"))
    )
    (net (code "71") (name "Net-(IC3-CV)") (class "Default")
      (node (ref "IC3") (pin "5") (pinfunction "CV_5") (pintype "input"))
      (node (ref "R3") (pin "1") (pinfunction "1_1") (pintype "passive"))
      (node (ref "T1") (pin "C") (pinfunction "C_C") (pintype "passive"))
    )
    (net (code "72") (name "Net-(IC3-DIS)") (class "Default")
      (node (ref "IC3") (pin "7") (pinfunction "DIS_7") (pintype "input"))
      (node (ref "R1") (pin "1") (pinfunction "1_1") (pintype "passive"))
      (node (ref "R2") (pin "2") (pinfunction "2_2") (pintype "passive"))
    )
    (net (code "73") (name "Net-(IC3-Q)") (class "Default")
      (node (ref "IC3") (pin "3") (pinfunction "Q_3") (pintype "output"))
      (node (ref "T2") (pin "1") (pinfunction "G_1") (pintype "passive"))
    )
    (net (code "74") (name "Net-(IC3-THR)") (class "Default")
      (node (ref "C2") (pin "1") (pinfunction "1_1") (pintype "passive"))
      (node (ref "IC3") (pin "2") (pinfunction "TR_2") (pintype "input"))
      (node (ref "IC3") (pin "6") (pinfunction "THR_6") (pintype "input"))
      (node (ref "R2") (pin "1") (pinfunction "1_1") (pintype "passive"))
    )
    (net (code "75") (name "Net-(IC4-PB0(ICP))") (class "Default")
      (node (ref "IC4") (pin "12") (pinfunction "PB0(ICP)_12") (pintype "bidirectional"))
      (node (ref "T5") (pin "1") (pinfunction "G_1") (pintype "passive"))
    )
    (net (code "76") (name "Net-(IC4-PB1(OC1A))") (class "Default")
      (node (ref "IC4") (pin "13") (pinfunction "PB1(OC1A)_13") (pintype "bidirectional"))
      (node (ref "T6") (pin "1") (pinfunction "G_1") (pintype "passive"))
    )
    (net (code "77") (name "Net-(IC4-PB3(MOSI{slash}OC2))") (class "Default")
      (node (ref "IC4") (pin "15") (pinfunction "PB3(MOSI/OC2)_15") (pintype "bidirectional"))
      (node (ref "MOSI") (pin "MP") (pinfunction "MP_MP") (pintype "passive"))
      (node (ref "T10") (pin "1") (pinfunction "G_1") (pintype "passive"))
    )
    (net (code "78") (name "Net-(IC4-PB4(MISO))") (class "Default")
      (node (ref "IC4") (pin "16") (pinfunction "PB4(MISO)_16") (pintype "bidirectional"))
      (node (ref "MISO") (pin "MP") (pinfunction "MP_MP") (pintype "passive"))
    )
    (net (code "79") (name "Net-(IC4-PB5(SCK))") (class "Default")
      (node (ref "IC4") (pin "17") (pinfunction "PB5(SCK)_17") (pintype "bidirectional"))
      (node (ref "SCK") (pin "MP") (pinfunction "MP_MP") (pintype "passive"))
      (node (ref "T3") (pin "1") (pinfunction "G_1") (pintype "passive"))
    )
    (net (code "80") (name "Net-(IC4-PB6(XTAL1{slash}TOSC1))") (class "Default")
      (node (ref "C9") (pin "1") (pinfunction "1_1") (pintype "passive"))
      (node (ref "IC4") (pin "7") (pinfunction "PB6(XTAL1/TOSC1)_7") (pintype "bidirectional"))
      (node (ref "Q1") (pin "1") (pinfunction "1_1") (pintype "passive"))
    )
    (net (code "81") (name "Net-(IC4-PB7(XTAL2{slash}TOSC2))") (class "Default")
      (node (ref "C8") (pin "1") (pinfunction "1_1") (pintype "passive"))
      (node (ref "IC4") (pin "8") (pinfunction "PB7(XTAL2/TOSC2)_8") (pintype "bidirectional"))
      (node (ref "Q1") (pin "2") (pinfunction "2_2") (pintype "passive"))
    )
    (net (code "82") (name "Net-(IC4-PC0(ADC0))") (class "Default")
      (node (ref "IC4") (pin "23") (pinfunction "PC0(ADC0)_23") (pintype "bidirectional"))
      (node (ref "T9") (pin "1") (pinfunction "G_1") (pintype "passive"))
    )
    (net (code "83") (name "Net-(IC4-PC1(ADC1))") (class "Default")
      (node (ref "IC4") (pin "24") (pinfunction "PC1(ADC1)_24") (pintype "bidirectional"))
      (node (ref "T8") (pin "1") (pinfunction "G_1") (pintype "passive"))
    )
    (net (code "84") (name "Net-(IC4-PC2(ADC2))") (class "Default")
      (node (ref "IC4") (pin "25") (pinfunction "PC2(ADC2)_25") (pintype "bidirectional"))
      (node (ref "T7") (pin "1") (pinfunction "G_1") (pintype "passive"))
    )
    (net (code "85") (name "Net-(IC4-PC6({slash}RESET))") (class "Default")
      (node (ref "IC4") (pin "29") (pinfunction "PC6(/RESET)_29") (pintype "bidirectional"))
      (node (ref "R39") (pin "1") (pinfunction "1_1") (pintype "passive"))
      (node (ref "RST") (pin "MP") (pinfunction "MP_MP") (pintype "passive"))
    )
    (net (code "86") (name "Net-(IC4-PD7(AIN1))") (class "Default")
      (node (ref "IC4") (pin "11") (pinfunction "PD7(AIN1)_11") (pintype "bidirectional"))
      (node (ref "T4") (pin "1") (pinfunction "G_1") (pintype "passive"))
    )
    (net (code "87") (name "Net-(L1-2)") (class "Default")
      (node (ref "D1") (pin "A") (pinfunction "A_A") (pintype "passive"))
      (node (ref "L1") (pin "P$2") (pinfunction "2_P$2") (pintype "passive"))
      (node (ref "R4") (pin "2") (pinfunction "2_2") (pintype "passive"))
      (node (ref "T2") (pin "3") (pinfunction "D_3") (pintype "passive"))
    )
    (net (code "88") (name "Net-(N1-PadA)") (class "Default")
      (node (ref "N1") (pin "A") (pinfunction "A_A") (pintype "bidirectional"))
      (node (ref "R12") (pin "1") (pinfunction "1_1") (pintype "passive"))
    )
    (net (code "89") (name "Net-(N2-PadA)") (class "Default")
      (node (ref "N2") (pin "A") (pinfunction "A_A") (pintype "bidirectional"))
      (node (ref "R11") (pin "1") (pinfunction "1_1") (pintype "passive"))
    )
    (net (code "90") (name "Net-(N3-PadA)") (class "Default")
      (node (ref "N3") (pin "A") (pinfunction "A_A") (pintype "bidirectional"))
      (node (ref "R10") (pin "1") (pinfunction "1_1") (pintype "passive"))
    )
    (net (code "91") (name "Net-(N4-PadA)") (class "Default")
      (node (ref "N4") (pin "A") (pinfunction "A_A") (pintype "bidirectional"))
      (node (ref "R9") (pin "1") (pinfunction "1_1") (pintype "passive"))
    )
    (net (code "92") (name "Net-(N5-PadA)") (class "Default")
      (node (ref "N5") (pin "A") (pinfunction "A_A") (pintype "bidirectional"))
      (node (ref "R8") (pin "1") (pinfunction "1_1") (pintype "passive"))
    )
    (net (code "93") (name "Net-(N6-PadA)") (class "Default")
      (node (ref "N6") (pin "A") (pinfunction "A_A") (pintype "bidirectional"))
      (node (ref "R7") (pin "1") (pinfunction "1_1") (pintype "passive"))
    )
    (net (code "94") (name "Net-(P1-Pad1)") (class "Default")
      (node (ref "P1") (pin "1") (pinfunction "1_1") (pintype "passive"))
      (node (ref "P1") (pin "3") (pinfunction "3_3") (pintype "passive"))
      (node (ref "R5") (pin "1") (pinfunction "1_1") (pintype "passive"))
      (node (ref "T1") (pin "B") (pinfunction "B_B") (pintype "passive"))
    )
    (net (code "95") (name "Net-(P1-Pad2)") (class "Default")
      (node (ref "P1") (pin "2") (pinfunction "2_2") (pintype "passive"))
      (node (ref "R6") (pin "2") (pinfunction "2_2") (pintype "passive"))
    )
    (net (code "96") (name "Net-(U$1A-ANODE)") (class "Default")
      (node (ref "R17") (pin "1") (pinfunction "1_1") (pintype "passive"))
      (node (ref "U$1") (pin "B_ANODE") (pinfunction "ANODE_B_ANODE") (pintype "bidirectional"))
    )
    (net (code "97") (name "Net-(U$1B-ANODE)") (class "Default")
      (node (ref "R16") (pin "1") (pinfunction "1_1") (pintype "passive"))
      (node (ref "U$1") (pin "G_ANODE") (pinfunction "ANODE_G_ANODE") (pintype "bidirectional"))
    )
    (net (code "98") (name "Net-(U$1C-ANODE)") (class "Default")
      (node (ref "R18") (pin "1") (pinfunction "1_1") (pintype "passive"))
      (node (ref "U$1") (pin "R_ANODE") (pinfunction "ANODE_R_ANODE") (pintype "bidirectional"))
    )
    (net (code "99") (name "Net-(U$3A-ANODE)") (class "Default")
      (node (ref "R20") (pin "1") (pinfunction "1_1") (pintype "passive"))
      (node (ref "U$3") (pin "B_ANODE") (pinfunction "ANODE_B_ANODE") (pintype "bidirectional"))
    )
    (net (code "100") (name "Net-(U$3B-ANODE)") (class "Default")
      (node (ref "R19") (pin "1") (pinfunction "1_1") (pintype "passive"))
      (node (ref "U$3") (pin "G_ANODE") (pinfunction "ANODE_G_ANODE") (pintype "bidirectional"))
    )
    (net (code "101") (name "Net-(U$3C-ANODE)") (class "Default")
      (node (ref "R21") (pin "1") (pinfunction "1_1") (pintype "passive"))
      (node (ref "U$3") (pin "R_ANODE") (pinfunction "ANODE_R_ANODE") (pintype "bidirectional"))
    )
    (net (code "102") (name "Net-(U$4A-ANODE)") (class "Default")
      (node (ref "R23") (pin "1") (pinfunction "1_1") (pintype "passive"))
      (node (ref "U$4") (pin "B_ANODE") (pinfunction "ANODE_B_ANODE") (pintype "bidirectional"))
    )
    (net (code "103") (name "Net-(U$4B-ANODE)") (class "Default")
      (node (ref "R22") (pin "1") (pinfunction "1_1") (pintype "passive"))
      (node (ref "U$4") (pin "G_ANODE") (pinfunction "ANODE_G_ANODE") (pintype "bidirectional"))
    )
    (net (code "104") (name "Net-(U$4C-ANODE)") (class "Default")
      (node (ref "R24") (pin "1") (pinfunction "1_1") (pintype "passive"))
      (node (ref "U$4") (pin "R_ANODE") (pinfunction "ANODE_R_ANODE") (pintype "bidirectional"))
    )
    (net (code "105") (name "Net-(U$5A-ANODE)") (class "Default")
      (node (ref "R26") (pin "1") (pinfunction "1_1") (pintype "passive"))
      (node (ref "U$5") (pin "B_ANODE") (pinfunction "ANODE_B_ANODE") (pintype "bidirectional"))
    )
    (net (code "106") (name "Net-(U$5B-ANODE)") (class "Default")
      (node (ref "R25") (pin "1") (pinfunction "1_1") (pintype "passive"))
      (node (ref "U$5") (pin "G_ANODE") (pinfunction "ANODE_G_ANODE") (pintype "bidirectional"))
    )
    (net (code "107") (name "Net-(U$5C-ANODE)") (class "Default")
      (node (ref "R27") (pin "1") (pinfunction "1_1") (pintype "passive"))
      (node (ref "U$5") (pin "R_ANODE") (pinfunction "ANODE_R_ANODE") (pintype "bidirectional"))
    )
    (net (code "108") (name "Net-(U$6A-ANODE)") (class "Default")
      (node (ref "R29") (pin "1") (pinfunction "1_1") (pintype "passive"))
      (node (ref "U$6") (pin "B_ANODE") (pinfunction "ANODE_B_ANODE") (pintype "bidirectional"))
    )
    (net (code "109") (name "Net-(U$6B-ANODE)") (class "Default")
      (node (ref "R28") (pin "1") (pinfunction "1_1") (pintype "passive"))
      (node (ref "U$6") (pin "G_ANODE") (pinfunction "ANODE_G_ANODE") (pintype "bidirectional"))
    )
    (net (code "110") (name "Net-(U$6C-ANODE)") (class "Default")
      (node (ref "R30") (pin "1") (pinfunction "1_1") (pintype "passive"))
      (node (ref "U$6") (pin "R_ANODE") (pinfunction "ANODE_R_ANODE") (pintype "bidirectional"))
    )
    (net (code "111") (name "Net-(U$7A-ANODE)") (class "Default")
      (node (ref "R35") (pin "1") (pinfunction "1_1") (pintype "passive"))
      (node (ref "U$7") (pin "B_ANODE") (pinfunction "ANODE_B_ANODE") (pintype "bidirectional"))
    )
    (net (code "112") (name "Net-(U$7B-ANODE)") (class "Default")
      (node (ref "R31") (pin "1") (pinfunction "1_1") (pintype "passive"))
      (node (ref "U$7") (pin "G_ANODE") (pinfunction "ANODE_G_ANODE") (pintype "bidirectional"))
    )
    (net (code "113") (name "Net-(U$7C-ANODE)") (class "Default")
      (node (ref "R36") (pin "1") (pinfunction "1_1") (pintype "passive"))
      (node (ref "U$7") (pin "R_ANODE") (pinfunction "ANODE_R_ANODE") (pintype "bidirectional"))
    )
    (net (code "114") (name "V+") (class "Default")
      (node (ref "C4") (pin "+") (pinfunction "+_+") (pintype "passive"))
      (node (ref "D1") (pin "K") (pinfunction "C_K") (pintype "passive"))
      (node (ref "R10") (pin "2") (pinfunction "2_2") (pintype "passive"))
      (node (ref "R11") (pin "2") (pinfunction "2_2") (pintype "passive"))
      (node (ref "R12") (pin "2") (pinfunction "2_2") (pintype "passive"))
      (node (ref "R13") (pin "2") (pinfunction "2_2") (pintype "passive"))
      (node (ref "R32") (pin "2") (pinfunction "2_2") (pintype "passive"))
      (node (ref "R33") (pin "2") (pinfunction "2_2") (pintype "passive"))
      (node (ref "R46") (pin "2") (pinfunction "2_2") (pintype "passive"))
      (node (ref "R5") (pin "2") (pinfunction "2_2") (pintype "passive"))
      (node (ref "R7") (pin "2") (pinfunction "2_2") (pintype "passive"))
      (node (ref "R8") (pin "2") (pinfunction "2_2") (pintype "passive"))
      (node (ref "R9") (pin "2") (pinfunction "2_2") (pintype "passive"))
    )
    (net (code "115") (name "unconnected-(IC1-HVOUT19-Pad4)") (class "Default")
      (node (ref "IC1") (pin "4") (pinfunction "HVOUT19_4") (pintype "bidirectional"))
    )
    (net (code "116") (name "unconnected-(IC1-HVOUT20-Pad3)") (class "Default")
      (node (ref "IC1") (pin "3") (pinfunction "HVOUT20_3") (pintype "bidirectional"))
    )
    (net (code "117") (name "unconnected-(IC1-HVOUT21-Pad2)") (class "Default")
      (node (ref "IC1") (pin "2") (pinfunction "HVOUT21_2") (pintype "bidirectional"))
    )
    (net (code "118") (name "unconnected-(IC1-HVOUT22-Pad1)") (class "Default")
      (node (ref "IC1") (pin "1") (pinfunction "HVOUT22_1") (pintype "bidirectional"))
    )
    (net (code "119") (name "unconnected-(IC1-HVOUT23-Pad44)") (class "Default")
      (node (ref "IC1") (pin "44") (pinfunction "HVOUT23_44") (pintype "bidirectional"))
    )
    (net (code "120") (name "unconnected-(IC1-HVOUT24-Pad43)") (class "Default")
      (node (ref "IC1") (pin "43") (pinfunction "HVOUT24_43") (pintype "bidirectional"))
    )
    (net (code "121") (name "unconnected-(IC1-HVOUT28-Pad39)") (class "Default")
      (node (ref "IC1") (pin "39") (pinfunction "HVOUT28_39") (pintype "bidirectional"))
    )
    (net (code "122") (name "unconnected-(IC1-HVOUT29-Pad38)") (class "Default")
      (node (ref "IC1") (pin "38") (pinfunction "HVOUT29_38") (pintype "bidirectional"))
    )
    (net (code "123") (name "unconnected-(IC1-HVOUT30-Pad37)") (class "Default")
      (node (ref "IC1") (pin "37") (pinfunction "HVOUT30_37") (pintype "bidirectional"))
    )
    (net (code "124") (name "unconnected-(IC1-HVOUT31-Pad36)") (class "Default")
      (node (ref "IC1") (pin "36") (pinfunction "HVOUT31_36") (pintype "bidirectional"))
    )
    (net (code "125") (name "unconnected-(IC1-HVOUT32-Pad35)") (class "Default")
      (node (ref "IC1") (pin "35") (pinfunction "HVOUT32_35") (pintype "bidirectional"))
    )
    (net (code "126") (name "unconnected-(IC2-DATA_OUT-Pad23)") (class "Default")
      (node (ref "IC2") (pin "23") (pinfunction "DATA_OUT_23") (pintype "output"))
    )
    (net (code "127") (name "unconnected-(IC2-HVOUT19-Pad4)") (class "Default")
      (node (ref "IC2") (pin "4") (pinfunction "HVOUT19_4") (pintype "bidirectional"))
    )
    (net (code "128") (name "unconnected-(IC2-HVOUT20-Pad3)") (class "Default")
      (node (ref "IC2") (pin "3") (pinfunction "HVOUT20_3") (pintype "bidirectional"))
    )
    (net (code "129") (name "unconnected-(IC2-HVOUT21-Pad2)") (class "Default")
      (node (ref "IC2") (pin "2") (pinfunction "HVOUT21_2") (pintype "bidirectional"))
    )
    (net (code "130") (name "unconnected-(IC2-HVOUT22-Pad1)") (class "Default")
      (node (ref "IC2") (pin "1") (pinfunction "HVOUT22_1") (pintype "bidirectional"))
    )
    (net (code "131") (name "unconnected-(IC4-ADC6-Pad19)") (class "Default")
      (node (ref "IC4") (pin "19") (pinfunction "ADC6_19") (pintype "bidirectional"))
    )
    (net (code "132") (name "unconnected-(IC4-ADC7-Pad22)") (class "Default")
      (node (ref "IC4") (pin "22") (pinfunction "ADC7_22") (pintype "bidirectional"))
    )
    (net (code "133") (name "unconnected-(IC4-AREF-Pad20)") (class "Default")
      (node (ref "IC4") (pin "20") (pinfunction "AREF_20") (pintype "passive"))
    )
    (net (code "134") (name "unconnected-(IC4-PB2(SS{slash}OC1B)-Pad14)") (class "Default")
      (node (ref "IC4") (pin "14") (pinfunction "PB2(SS/OC1B)_14") (pintype "bidirectional"))
    )
    (net (code "135") (name "unconnected-(IC4-PC3(ADC3)-Pad26)") (class "Default")
      (node (ref "IC4") (pin "26") (pinfunction "PC3(ADC3)_26") (pintype "bidirectional"))
    )
    (net (code "136") (name "unconnected-(IC4-PC4(ADC4{slash}SDA)-Pad27)") (class "Default")
      (node (ref "IC4") (pin "27") (pinfunction "PC4(ADC4/SDA)_27") (pintype "bidirectional"))
    )
    (net (code "137") (name "unconnected-(IC4-PC5(ADC5{slash}SCL)-Pad28)") (class "Default")
      (node (ref "IC4") (pin "28") (pinfunction "PC5(ADC5/SCL)_28") (pintype "bidirectional"))
    )
    (net (code "138") (name "unconnected-(IC4-PD4(XCK{slash}T0)-Pad2)") (class "Default")
      (node (ref "IC4") (pin "2") (pinfunction "PD4(XCK/T0)_2") (pintype "bidirectional"))
    )
    (net (code "139") (name "unconnected-(IC4-PD5(T1)-Pad9)") (class "Default")
      (node (ref "IC4") (pin "9") (pinfunction "PD5(T1)_9") (pintype "bidirectional"))
    )
    (net (code "140") (name "unconnected-(IC4-PD6(AIN0)-Pad10)") (class "Default")
      (node (ref "IC4") (pin "10") (pinfunction "PD6(AIN0)_10") (pintype "bidirectional"))
    )
    (net (code "141") (name "unconnected-(N1-Pad3)") (class "Default")
      (node (ref "N1") (pin "3") (pinfunction "3_3") (pintype "bidirectional"))
    )
    (net (code "142") (name "unconnected-(N1-Pad4)") (class "Default")
      (node (ref "N1") (pin "4") (pinfunction "4_4") (pintype "bidirectional"))
    )
    (net (code "143") (name "unconnected-(N1-Pad5)") (class "Default")
      (node (ref "N1") (pin "5") (pinfunction "5_5") (pintype "bidirectional"))
    )
    (net (code "144") (name "unconnected-(N1-Pad6)") (class "Default")
      (node (ref "N1") (pin "6") (pinfunction "6_6") (pintype "bidirectional"))
    )
    (net (code "145") (name "unconnected-(N1-Pad7)") (class "Default")
      (node (ref "N1") (pin "7") (pinfunction "7_7") (pintype "bidirectional"))
    )
    (net (code "146") (name "unconnected-(N1-Pad8)") (class "Default")
      (node (ref "N1") (pin "8") (pinfunction "8_8") (pintype "bidirectional"))
    )
    (net (code "147") (name "unconnected-(N1-Pad9)") (class "Default")
      (node (ref "N1") (pin "9") (pinfunction "9_9") (pintype "bidirectional"))
    )
    (net (code "148") (name "unconnected-(N1-PadLHDP)") (class "Default")
      (node (ref "N1") (pin "LHDP") (pinfunction "LHDP_LHDP") (pintype "bidirectional"))
    )
    (net (code "149") (name "unconnected-(N1-PadRHDP)") (class "Default")
      (node (ref "N1") (pin "RHDP") (pinfunction "RHDP_RHDP") (pintype "bidirectional"))
    )
    (net (code "150") (name "unconnected-(N2-PadLHDP)") (class "Default")
      (node (ref "N2") (pin "LHDP") (pinfunction "LHDP_LHDP") (pintype "bidirectional"))
    )
    (net (code "151") (name "unconnected-(N2-PadRHDP)") (class "Default")
      (node (ref "N2") (pin "RHDP") (pinfunction "RHDP_RHDP") (pintype "bidirectional"))
    )
    (net (code "152") (name "unconnected-(N3-Pad6)") (class "Default")
      (node (ref "N3") (pin "6") (pinfunction "6_6") (pintype "bidirectional"))
    )
    (net (code "153") (name "unconnected-(N3-Pad7)") (class "Default")
      (node (ref "N3") (pin "7") (pinfunction "7_7") (pintype "bidirectional"))
    )
    (net (code "154") (name "unconnected-(N3-Pad8)") (class "Default")
      (node (ref "N3") (pin "8") (pinfunction "8_8") (pintype "bidirectional"))
    )
    (net (code "155") (name "unconnected-(N3-Pad9)") (class "Default")
      (node (ref "N3") (pin "9") (pinfunction "9_9") (pintype "bidirectional"))
    )
    (net (code "156") (name "unconnected-(N3-PadLHDP)") (class "Default")
      (node (ref "N3") (pin "LHDP") (pinfunction "LHDP_LHDP") (pintype "bidirectional"))
    )
    (net (code "157") (name "unconnected-(N3-PadRHDP)") (class "Default")
      (node (ref "N3") (pin "RHDP") (pinfunction "RHDP_RHDP") (pintype "bidirectional"))
    )
    (net (code "158") (name "unconnected-(N4-PadLHDP)") (class "Default")
      (node (ref "N4") (pin "LHDP") (pinfunction "LHDP_LHDP") (pintype "bidirectional"))
    )
    (net (code "159") (name "unconnected-(N4-PadRHDP)") (class "Default")
      (node (ref "N4") (pin "RHDP") (pinfunction "RHDP_RHDP") (pintype "bidirectional"))
    )
    (net (code "160") (name "unconnected-(N5-Pad6)") (class "Default")
      (node (ref "N5") (pin "6") (pinfunction "6_6") (pintype "bidirectional"))
    )
    (net (code "161") (name "unconnected-(N5-Pad7)") (class "Default")
      (node (ref "N5") (pin "7") (pinfunction "7_7") (pintype "bidirectional"))
    )
    (net (code "162") (name "unconnected-(N5-Pad8)") (class "Default")
      (node (ref "N5") (pin "8") (pinfunction "8_8") (pintype "bidirectional"))
    )
    (net (code "163") (name "unconnected-(N5-Pad9)") (class "Default")
      (node (ref "N5") (pin "9") (pinfunction "9_9") (pintype "bidirectional"))
    )
    (net (code "164") (name "unconnected-(N5-PadLHDP)") (class "Default")
      (node (ref "N5") (pin "LHDP") (pinfunction "LHDP_LHDP") (pintype "bidirectional"))
    )
    (net (code "165") (name "unconnected-(N5-PadRHDP)") (class "Default")
      (node (ref "N5") (pin "RHDP") (pinfunction "RHDP_RHDP") (pintype "bidirectional"))
    )
    (net (code "166") (name "unconnected-(N6-PadLHDP)") (class "Default")
      (node (ref "N6") (pin "LHDP") (pinfunction "LHDP_LHDP") (pintype "bidirectional"))
    )
    (net (code "167") (name "unconnected-(N6-PadRHDP)") (class "Default")
      (node (ref "N6") (pin "RHDP") (pinfunction "RHDP_RHDP") (pintype "bidirectional"))
    )
    (net (code "168") (name "unconnected-(U$2-PadGPIO0)") (class "Default")
      (node (ref "U$2") (pin "GPIO0") (pinfunction "GPIO0_GPIO0") (pintype "bidirectional"))
    )
    (net (code "169") (name "unconnected-(U$2-PadGPIO2)") (class "Default")
      (node (ref "U$2") (pin "GPIO2") (pinfunction "GPIO2_GPIO2") (pintype "bidirectional"))
    )
  )
)
